# ESP01-Schematic.net
KiCad netlist of a schematic drawn in Altium Designer
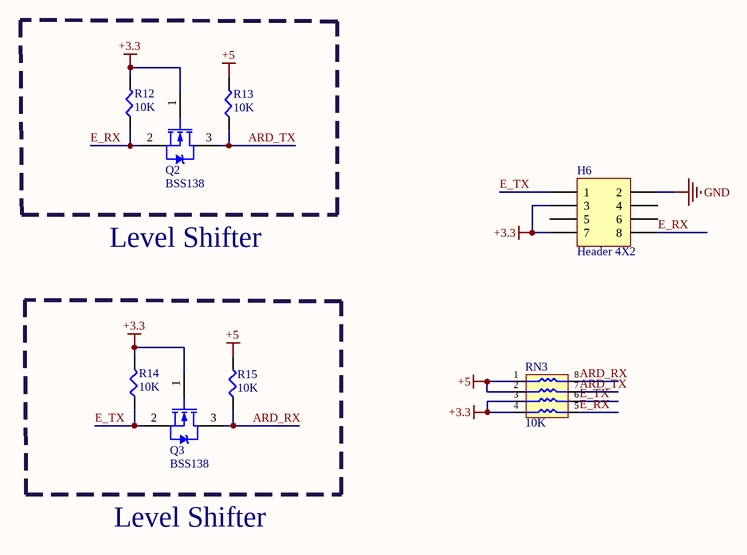
[diagram p0: ESP01-Schematic.SchDoc]

(export (version "E")
  (design (tool "Eeschema 10.0.6"))
  (components
    (comp (ref "H6")
      (value "Header 4X2")
      (footprint "HDR2X4")
      (description "Header, 4-Pin, Dual row")
      (fields (field (name "PUBLISHER") "Altium Limited"))
      (libsource (lib "Miscellaneous Connectors") (part "Header 4X2"))
    )
    (comp (ref "Q2")
      (value "BSS138")
      (footprint "SMT_TRIODE_NPN")
      (description "N-Channel Power MOSFET")
      (fields (field (name "PUBLISHER") "Altium Limited"))
      (libsource (lib "BSS138") (part "BSS138"))
    )
    (comp (ref "Q3")
      (value "BSS138")
      (footprint "SMT_TRIODE_NPN")
      (description "N-Channel Power MOSFET")
      (fields (field (name "PUBLISHER") "Altium Limited"))
      (libsource (lib "BSS138") (part "BSS138"))
    )
    (comp (ref "R12")
      (value "10K")
      (description "RES SMD 1 OHM 1% 1/3W 0805")
      (fields (field (name "PART NUMBER") "ERJ-6BQF1R0V") (field (name "DIGI-KEY PART NUMBER") "P17499CT-ND"))
      (libsource (lib "Res0805") (part "ERJ-6BQF1R0V"))
    )
    (comp (ref "R13")
      (value "10K")
      (description "RES SMD 1 OHM 1% 1/3W 0805")
      (fields (field (name "PART NUMBER") "ERJ-6BQF1R0V") (field (name "DIGI-KEY PART NUMBER") "P17499CT-ND"))
      (libsource (lib "Res0805") (part "ERJ-6BQF1R0V"))
    )
    (comp (ref "R14")
      (value "10K")
      (description "RES SMD 1 OHM 1% 1/3W 0805")
      (fields (field (name "PART NUMBER") "ERJ-6BQF1R0V") (field (name "DIGI-KEY PART NUMBER") "P17499CT-ND"))
      (libsource (lib "Res0805") (part "ERJ-6BQF1R0V"))
    )
    (comp (ref "R15")
      (value "10K")
      (description "RES SMD 1 OHM 1% 1/3W 0805")
      (fields (field (name "PART NUMBER") "ERJ-6BQF1R0V") (field (name "DIGI-KEY PART NUMBER") "P17499CT-ND"))
      (libsource (lib "Res0805") (part "ERJ-6BQF1R0V"))
    )
    (comp (ref "RN3")
      (value "10K")
      (footprint "RA0603-8")
      (fields (field (name "MF") "Yageo") (field (name "MP") "YC164-JR-07330RL"))
      (libsource (lib "ResNetwork(SMD)") (part "RES_NETWORK"))
    )
  )
  (nets
    (net (code "1") (name "+3.3") (class "Default")
      (node (ref "H6") (pin "3") (pinfunction "3_3") (pintype "passive"))
      (node (ref "H6") (pin "7") (pinfunction "7_7") (pintype "passive"))
      (node (ref "Q2") (pin "1") (pinfunction "G_1") (pintype "passive"))
      (node (ref "Q3") (pin "1") (pinfunction "G_1") (pintype "passive"))
      (node (ref "R12") (pin "2") (pinfunction "2_2") (pintype "passive"))
      (node (ref "R14") (pin "2") (pinfunction "2_2") (pintype "passive"))
      (node (ref "RN3") (pin "3") (pinfunction "3_3") (pintype "passive"))
      (node (ref "RN3") (pin "4") (pinfunction "4_4") (pintype "passive"))
    )
    (net (code "2") (name "+5") (class "Default")
      (node (ref "R13") (pin "2") (pinfunction "2_2") (pintype "passive"))
      (node (ref "R15") (pin "2") (pinfunction "2_2") (pintype "passive"))
      (node (ref "RN3") (pin "1") (pinfunction "1_1") (pintype "passive"))
      (node (ref "RN3") (pin "2") (pinfunction "2_2") (pintype "passive"))
    )
    (net (code "3") (name "/ARD_RX") (class "Default")
      (node (ref "Q3") (pin "3") (pinfunction "D_3") (pintype "passive"))
      (node (ref "R15") (pin "1") (pinfunction "1_1") (pintype "passive"))
      (node (ref "RN3") (pin "8") (pinfunction "8_8") (pintype "passive"))
    )
    (net (code "4") (name "/ARD_TX") (class "Default")
      (node (ref "Q2") (pin "3") (pinfunction "D_3") (pintype "passive"))
      (node (ref "R13") (pin "1") (pinfunction "1_1") (pintype "passive"))
      (node (ref "RN3") (pin "7") (pinfunction "7_7") (pintype "passive"))
    )
    (net (code "5") (name "/E_RX") (class "Default")
      (node (ref "H6") (pin "8") (pinfunction "8_8") (pintype "passive"))
      (node (ref "Q2") (pin "2") (pinfunction "S_2") (pintype "passive"))
      (node (ref "R12") (pin "1") (pinfunction "1_1") (pintype "passive"))
      (node (ref "RN3") (pin "5") (pinfunction "5_5") (pintype "passive"))
    )
    (net (code "6") (name "/E_TX") (class "Default")
      (node (ref "H6") (pin "1") (pinfunction "1_1") (pintype "passive"))
      (node (ref "Q3") (pin "2") (pinfunction "S_2") (pintype "passive"))
      (node (ref "R14") (pin "1") (pinfunction "1_1") (pintype "passive"))
      (node (ref "RN3") (pin "6") (pinfunction "6_6") (pintype "passive"))
    )
    (net (code "7") (name "GND") (class "Default")
      (node (ref "H6") (pin "2") (pinfunction "2_2") (pintype "passive"))
    )
    (net (code "8") (name "unconnected-(H6-Pad4)") (class "Default")
      (node (ref "H6") (pin "4") (pinfunction "4_4") (pintype "passive"))
    )
    (net (code "9") (name "unconnected-(H6-Pad5)") (class "Default")
      (node (ref "H6") (pin "5") (pinfunction "5_5") (pintype "passive"))
    )
    (net (code "10") (name "unconnected-(H6-Pad6)") (class "Default")
      (node (ref "H6") (pin "6") (pinfunction "6_6") (pintype "passive"))
    )
  )
)
